# Schematic.net
KiCad netlist of a schematic drawn in Altium Designer
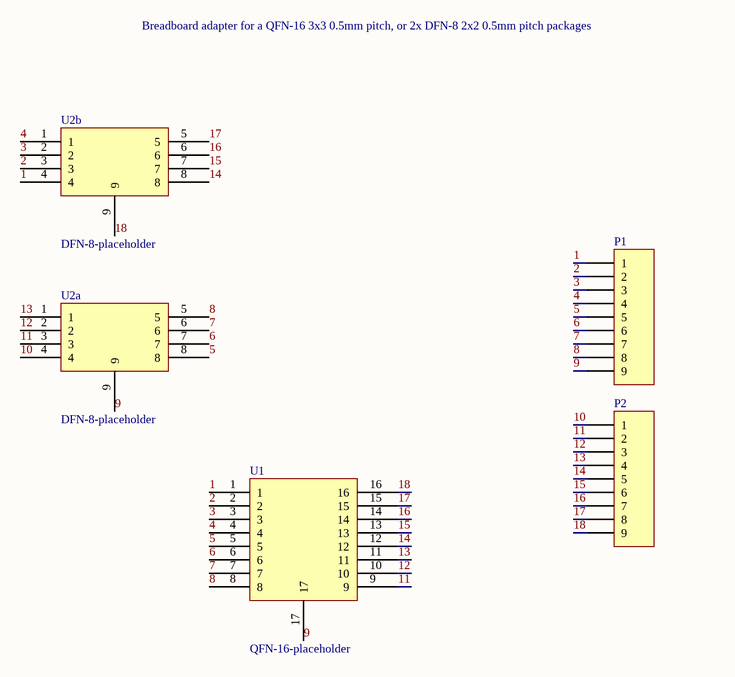
[diagram p0: Schematic.SchDoc]

(export (version "E")
  (design (tool "Eeschema 10.0.6"))
  (components
    (comp (ref "P1")
      (value "~")
      (footprint "HDR1X9")
      (description "Header, 9-Pin")
      (fields (field (name "PUBLISHER") "Altium Limited"))
      (libsource (lib "Miscellaneous Connectors") (part "Header 9"))
    )
    (comp (ref "P2")
      (value "~")
      (footprint "HDR1X9")
      (description "Header, 9-Pin")
      (fields (field (name "PUBLISHER") "Altium Limited"))
      (libsource (lib "Miscellaneous Connectors") (part "Header 9"))
    )
    (comp (ref "U1")
      (value "QFN-16-placeholder")
      (footprint "QFN,DFN:QFN50P300X300X100-17N")
      (libsource (lib "placeholders") (part "QFN-16-placeholder"))
    )
    (comp (ref "U2a")
      (value "DFN-8-placeholder")
      (footprint "SON50P200X200X60-9N")
      (libsource (lib "placeholders") (part "DFN-8-placeholder"))
    )
    (comp (ref "U2b")
      (value "DFN-8-placeholder")
      (footprint "SON50P200X200X60-9N")
      (libsource (lib "placeholders") (part "DFN-8-placeholder"))
    )
  )
  (nets
    (net (code "1") (name "/1") (class "Default")
      (node (ref "P1") (pin "1") (pinfunction "1_1") (pintype "passive"))
      (node (ref "U1") (pin "1") (pinfunction "1_1") (pintype "passive"))
      (node (ref "U2b") (pin "4") (pinfunction "4_4") (pintype "passive"))
    )
    (net (code "2") (name "/2") (class "Default")
      (node (ref "P1") (pin "2") (pinfunction "2_2") (pintype "passive"))
      (node (ref "U1") (pin "2") (pinfunction "2_2") (pintype "passive"))
      (node (ref "U2b") (pin "3") (pinfunction "3_3") (pintype "passive"))
    )
    (net (code "3") (name "/3") (class "Default")
      (node (ref "P1") (pin "3") (pinfunction "3_3") (pintype "passive"))
      (node (ref "U1") (pin "3") (pinfunction "3_3") (pintype "passive"))
      (node (ref "U2b") (pin "2") (pinfunction "2_2") (pintype "passive"))
    )
    (net (code "4") (name "/4") (class "Default")
      (node (ref "P1") (pin "4") (pinfunction "4_4") (pintype "passive"))
      (node (ref "U1") (pin "4") (pinfunction "4_4") (pintype "passive"))
      (node (ref "U2b") (pin "1") (pinfunction "1_1") (pintype "passive"))
    )
    (net (code "5") (name "/5") (class "Default")
      (node (ref "P1") (pin "5") (pinfunction "5_5") (pintype "passive"))
      (node (ref "U1") (pin "5") (pinfunction "5_5") (pintype "passive"))
      (node (ref "U2a") (pin "8") (pinfunction "8_8") (pintype "passive"))
    )
    (net (code "6") (name "/6") (class "Default")
      (node (ref "P1") (pin "6") (pinfunction "6_6") (pintype "passive"))
      (node (ref "U1") (pin "6") (pinfunction "6_6") (pintype "passive"))
      (node (ref "U2a") (pin "7") (pinfunction "7_7") (pintype "passive"))
    )
    (net (code "7") (name "/7") (class "Default")
      (node (ref "P1") (pin "7") (pinfunction "7_7") (pintype "passive"))
      (node (ref "U1") (pin "7") (pinfunction "7_7") (pintype "passive"))
      (node (ref "U2a") (pin "6") (pinfunction "6_6") (pintype "passive"))
    )
    (net (code "8") (name "/8") (class "Default")
      (node (ref "P1") (pin "8") (pinfunction "8_8") (pintype "passive"))
      (node (ref "U1") (pin "8") (pinfunction "8_8") (pintype "passive"))
      (node (ref "U2a") (pin "5") (pinfunction "5_5") (pintype "passive"))
    )
    (net (code "9") (name "/9") (class "Default")
      (node (ref "P1") (pin "9") (pinfunction "9_9") (pintype "passive"))
      (node (ref "U1") (pin "17") (pinfunction "17_17") (pintype "passive"))
      (node (ref "U2a") (pin "9") (pinfunction "9_9") (pintype "passive"))
    )
    (net (code "10") (name "/10") (class "Default")
      (node (ref "P2") (pin "1") (pinfunction "1_1") (pintype "passive"))
      (node (ref "U2a") (pin "4") (pinfunction "4_4") (pintype "passive"))
    )
    (net (code "11") (name "/11") (class "Default")
      (node (ref "P2") (pin "2") (pinfunction "2_2") (pintype "passive"))
      (node (ref "U1") (pin "9") (pinfunction "9_9") (pintype "passive"))
      (node (ref "U2a") (pin "3") (pinfunction "3_3") (pintype "passive"))
    )
    (net (code "12") (name "/12") (class "Default")
      (node (ref "P2") (pin "3") (pinfunction "3_3") (pintype "passive"))
      (node (ref "U1") (pin "10") (pinfunction "10_10") (pintype "passive"))
      (node (ref "U2a") (pin "2") (pinfunction "2_2") (pintype "passive"))
    )
    (net (code "13") (name "/13") (class "Default")
      (node (ref "P2") (pin "4") (pinfunction "4_4") (pintype "passive"))
      (node (ref "U1") (pin "11") (pinfunction "11_11") (pintype "passive"))
      (node (ref "U2a") (pin "1") (pinfunction "1_1") (pintype "passive"))
    )
    (net (code "14") (name "/14") (class "Default")
      (node (ref "P2") (pin "5") (pinfunction "5_5") (pintype "passive"))
      (node (ref "U1") (pin "12") (pinfunction "12_12") (pintype "passive"))
      (node (ref "U2b") (pin "8") (pinfunction "8_8") (pintype "passive"))
    )
    (net (code "15") (name "/15") (class "Default")
      (node (ref "P2") (pin "6") (pinfunction "6_6") (pintype "passive"))
      (node (ref "U1") (pin "13") (pinfunction "13_13") (pintype "passive"))
      (node (ref "U2b") (pin "7") (pinfunction "7_7") (pintype "passive"))
    )
    (net (code "16") (name "/16") (class "Default")
      (node (ref "P2") (pin "7") (pinfunction "7_7") (pintype "passive"))
      (node (ref "U1") (pin "14") (pinfunction "14_14") (pintype "passive"))
      (node (ref "U2b") (pin "6") (pinfunction "6_6") (pintype "passive"))
    )
    (net (code "17") (name "/17") (class "Default")
      (node (ref "P2") (pin "8") (pinfunction "8_8") (pintype "passive"))
      (node (ref "U1") (pin "15") (pinfunction "15_15") (pintype "passive"))
      (node (ref "U2b") (pin "5") (pinfunction "5_5") (pintype "passive"))
    )
    (net (code "18") (name "/18") (class "Default")
      (node (ref "P2") (pin "9") (pinfunction "9_9") (pintype "passive"))
      (node (ref "U1") (pin "16") (pinfunction "16_16") (pintype "passive"))
      (node (ref "U2b") (pin "9") (pinfunction "9_9") (pintype "passive"))
    )
  )
)
